# Sheet2.net
KiCad netlist of a schematic drawn in Altium Designer
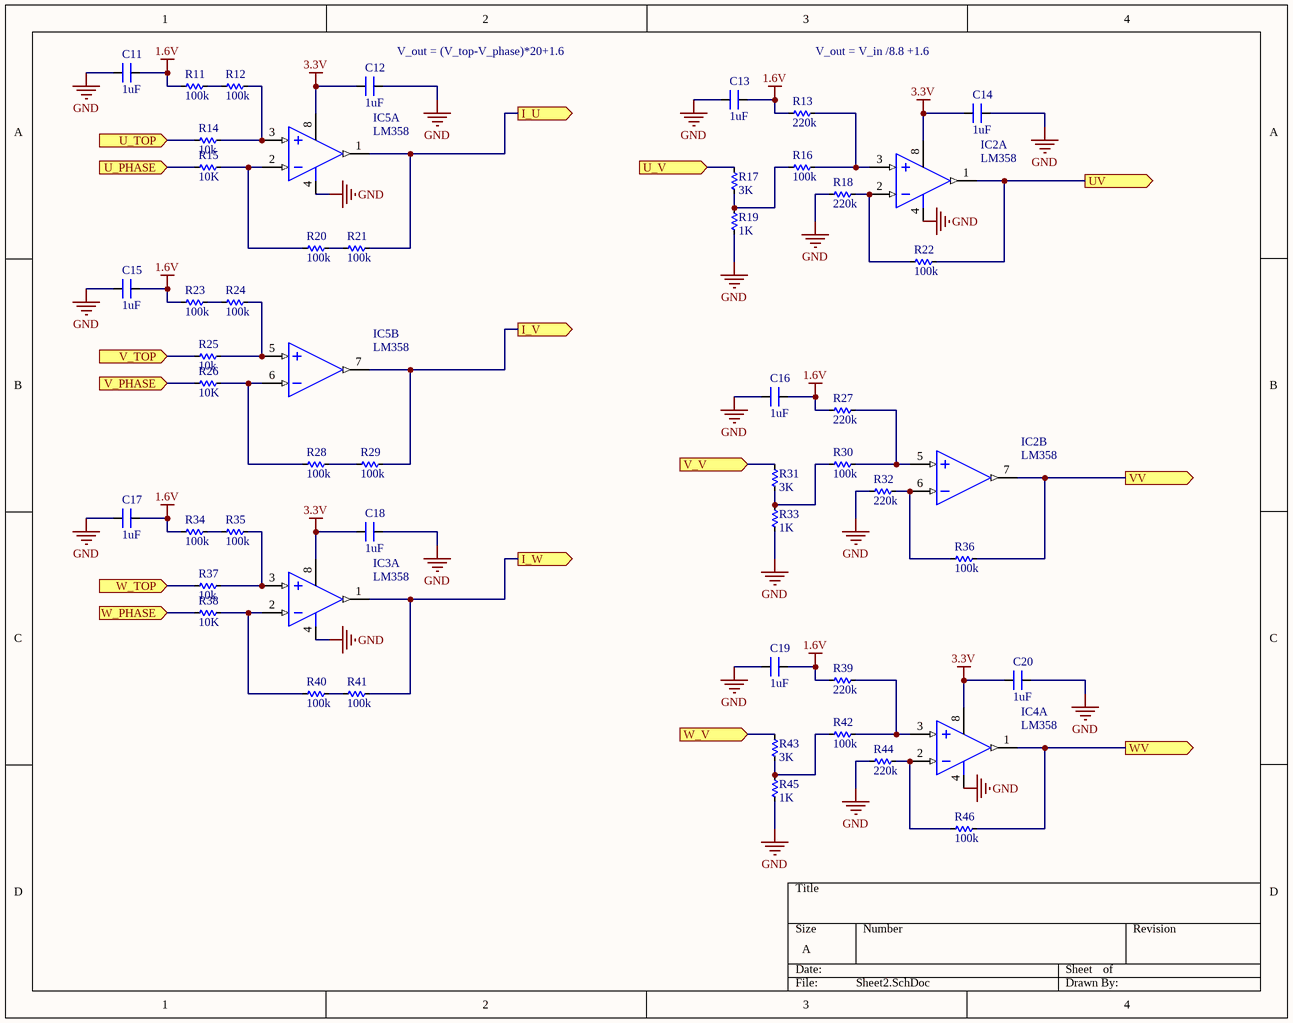
[diagram p0: Sheet2.SchDoc]

(export (version "E")
  (design (tool "Eeschema 10.0.6"))
  (components
    (comp (ref "C11")
      (value "1uF")
      (footprint "CN1")
      (description "Cap np  1pF - 472pF")
      (libsource (lib "syhaunguyen") (part "CN1"))
    )
    (comp (ref "C12")
      (value "1uF")
      (footprint "CN1")
      (description "Cap np  1pF - 472pF")
      (libsource (lib "syhaunguyen") (part "CN1"))
    )
    (comp (ref "C13")
      (value "1uF")
      (footprint "CN1")
      (description "Cap np  1pF - 472pF")
      (libsource (lib "syhaunguyen") (part "CN1"))
    )
    (comp (ref "C14")
      (value "1uF")
      (footprint "CN1")
      (description "Cap np  1pF - 472pF")
      (libsource (lib "syhaunguyen") (part "CN1"))
    )
    (comp (ref "C15")
      (value "1uF")
      (footprint "CN1")
      (description "Cap np  1pF - 472pF")
      (libsource (lib "syhaunguyen") (part "CN1"))
    )
    (comp (ref "C16")
      (value "1uF")
      (footprint "CN1")
      (description "Cap np  1pF - 472pF")
      (libsource (lib "syhaunguyen") (part "CN1"))
    )
    (comp (ref "C17")
      (value "1uF")
      (footprint "CN1")
      (description "Cap np  1pF - 472pF")
      (libsource (lib "syhaunguyen") (part "CN1"))
    )
    (comp (ref "C18")
      (value "1uF")
      (footprint "CN1")
      (description "Cap np  1pF - 472pF")
      (libsource (lib "syhaunguyen") (part "CN1"))
    )
    (comp (ref "C19")
      (value "1uF")
      (footprint "CN1")
      (description "Cap np  1pF - 472pF")
      (libsource (lib "syhaunguyen") (part "CN1"))
    )
    (comp (ref "C20")
      (value "1uF")
      (footprint "CN1")
      (description "Cap np  1pF - 472pF")
      (libsource (lib "syhaunguyen") (part "CN1"))
    )
    (comp (ref "IC2")
      (value "LM358")
      (footprint "DIP8")
      (description "Low-Power Dual Operational Amplifier")
      (libsource (lib "LIBRARY") (part "LM358"))
    )
    (comp (ref "IC3")
      (value "LM358")
      (footprint "DIP8")
      (description "Low-Power Dual Operational Amplifier")
      (libsource (lib "LIBRARY") (part "LM358"))
    )
    (comp (ref "IC4")
      (value "LM358")
      (footprint "DIP8")
      (description "Low-Power Dual Operational Amplifier")
      (libsource (lib "LIBRARY") (part "LM358"))
    )
    (comp (ref "IC5")
      (value "LM358")
      (footprint "DIP8")
      (description "Low-Power Dual Operational Amplifier")
      (libsource (lib "LIBRARY") (part "LM358"))
    )
    (comp (ref "R11")
      (value "100k")
      (footprint "RES-1/2W")
      (description "Res")
      (fields
        (field (name "MANUFACTURER") "Generic Components")
        (field (name "PUBLISHER") "Altium Hobart Technology Centre")
      )
      (libsource (lib "LIBRARY1") (part "Res"))
    )
    (comp (ref "R12")
      (value "100k")
      (footprint "RES-1/2W")
      (description "Res")
      (fields
        (field (name "MANUFACTURER") "Generic Components")
        (field (name "PUBLISHER") "Altium Hobart Technology Centre")
      )
      (libsource (lib "LIBRARY1") (part "Res"))
    )
    (comp (ref "R13")
      (value "220k")
      (footprint "RES-1/2W")
      (description "Res")
      (fields
        (field (name "MANUFACTURER") "Generic Components")
        (field (name "PUBLISHER") "Altium Hobart Technology Centre")
      )
      (libsource (lib "LIBRARY1") (part "Res"))
    )
    (comp (ref "R14")
      (value "10k")
      (footprint "RES-1/2W")
      (description "Res")
      (fields
        (field (name "MANUFACTURER") "Generic Components")
        (field (name "PUBLISHER") "Altium Hobart Technology Centre")
      )
      (libsource (lib "LIBRARY1") (part "Res"))
    )
    (comp (ref "R15")
      (value "10K")
      (footprint "RES-1/2W")
      (description "Res")
      (fields
        (field (name "MANUFACTURER") "Generic Components")
        (field (name "PUBLISHER") "Altium Hobart Technology Centre")
      )
      (libsource (lib "LIBRARY1") (part "Res"))
    )
    (comp (ref "R16")
      (value "100k")
      (footprint "RES-1/2W")
      (description "Res")
      (fields
        (field (name "MANUFACTURER") "Generic Components")
        (field (name "PUBLISHER") "Altium Hobart Technology Centre")
      )
      (libsource (lib "LIBRARY1") (part "Res"))
    )
    (comp (ref "R17")
      (value "3K")
      (footprint "RES-1/2W")
      (description "Res")
      (fields
        (field (name "MANUFACTURER") "Generic Components")
        (field (name "PUBLISHER") "Altium Hobart Technology Centre")
      )
      (libsource (lib "LIBRARY1") (part "Res"))
    )
    (comp (ref "R18")
      (value "220k")
      (footprint "RES-1/2W")
      (description "Res")
      (fields
        (field (name "MANUFACTURER") "Generic Components")
        (field (name "PUBLISHER") "Altium Hobart Technology Centre")
      )
      (libsource (lib "LIBRARY1") (part "Res"))
    )
    (comp (ref "R19")
      (value "1K")
      (footprint "RES-1/2W")
      (description "Res")
      (fields
        (field (name "MANUFACTURER") "Generic Components")
        (field (name "PUBLISHER") "Altium Hobart Technology Centre")
      )
      (libsource (lib "LIBRARY1") (part "Res"))
    )
    (comp (ref "R20")
      (value "100k")
      (footprint "RES-1/2W")
      (description "Res")
      (fields
        (field (name "MANUFACTURER") "Generic Components")
        (field (name "PUBLISHER") "Altium Hobart Technology Centre")
      )
      (libsource (lib "LIBRARY1") (part "Res"))
    )
    (comp (ref "R21")
      (value "100k")
      (footprint "RES-1/2W")
      (description "Res")
      (fields
        (field (name "MANUFACTURER") "Generic Components")
        (field (name "PUBLISHER") "Altium Hobart Technology Centre")
      )
      (libsource (lib "LIBRARY1") (part "Res"))
    )
    (comp (ref "R22")
      (value "100k")
      (footprint "RES-1/2W")
      (description "Res")
      (fields
        (field (name "MANUFACTURER") "Generic Components")
        (field (name "PUBLISHER") "Altium Hobart Technology Centre")
      )
      (libsource (lib "LIBRARY1") (part "Res"))
    )
    (comp (ref "R23")
      (value "100k")
      (footprint "RES-1/2W")
      (description "Res")
      (fields
        (field (name "MANUFACTURER") "Generic Components")
        (field (name "PUBLISHER") "Altium Hobart Technology Centre")
      )
      (libsource (lib "LIBRARY1") (part "Res"))
    )
    (comp (ref "R24")
      (value "100k")
      (footprint "RES-1/2W")
      (description "Res")
      (fields
        (field (name "MANUFACTURER") "Generic Components")
        (field (name "PUBLISHER") "Altium Hobart Technology Centre")
      )
      (libsource (lib "LIBRARY1") (part "Res"))
    )
    (comp (ref "R25")
      (value "10k")
      (footprint "RES-1/2W")
      (description "Res")
      (fields
        (field (name "MANUFACTURER") "Generic Components")
        (field (name "PUBLISHER") "Altium Hobart Technology Centre")
      )
      (libsource (lib "LIBRARY1") (part "Res"))
    )
    (comp (ref "R26")
      (value "10K")
      (footprint "RES-1/2W")
      (description "Res")
      (fields
        (field (name "MANUFACTURER") "Generic Components")
        (field (name "PUBLISHER") "Altium Hobart Technology Centre")
      )
      (libsource (lib "LIBRARY1") (part "Res"))
    )
    (comp (ref "R27")
      (value "220k")
      (footprint "RES-1/2W")
      (description "Res")
      (fields
        (field (name "MANUFACTURER") "Generic Components")
        (field (name "PUBLISHER") "Altium Hobart Technology Centre")
      )
      (libsource (lib "LIBRARY1") (part "Res"))
    )
    (comp (ref "R28")
      (value "100k")
      (footprint "RES-1/2W")
      (description "Res")
      (fields
        (field (name "MANUFACTURER") "Generic Components")
        (field (name "PUBLISHER") "Altium Hobart Technology Centre")
      )
      (libsource (lib "LIBRARY1") (part "Res"))
    )
    (comp (ref "R29")
      (value "100k")
      (footprint "RES-1/2W")
      (description "Res")
      (fields
        (field (name "MANUFACTURER") "Generic Components")
        (field (name "PUBLISHER") "Altium Hobart Technology Centre")
      )
      (libsource (lib "LIBRARY1") (part "Res"))
    )
    (comp (ref "R30")
      (value "100k")
      (footprint "RES-1/2W")
      (description "Res")
      (fields
        (field (name "MANUFACTURER") "Generic Components")
        (field (name "PUBLISHER") "Altium Hobart Technology Centre")
      )
      (libsource (lib "LIBRARY1") (part "Res"))
    )
    (comp (ref "R31")
      (value "3K")
      (footprint "RES-1/2W")
      (description "Res")
      (fields
        (field (name "MANUFACTURER") "Generic Components")
        (field (name "PUBLISHER") "Altium Hobart Technology Centre")
      )
      (libsource (lib "LIBRARY1") (part "Res"))
    )
    (comp (ref "R32")
      (value "220k")
      (footprint "RES-1/2W")
      (description "Res")
      (fields
        (field (name "MANUFACTURER") "Generic Components")
        (field (name "PUBLISHER") "Altium Hobart Technology Centre")
      )
      (libsource (lib "LIBRARY1") (part "Res"))
    )
    (comp (ref "R33")
      (value "1K")
      (footprint "RES-1/2W")
      (description "Res")
      (fields
        (field (name "MANUFACTURER") "Generic Components")
        (field (name "PUBLISHER") "Altium Hobart Technology Centre")
      )
      (libsource (lib "LIBRARY1") (part "Res"))
    )
    (comp (ref "R34")
      (value "100k")
      (footprint "RES-1/2W")
      (description "Res")
      (fields
        (field (name "MANUFACTURER") "Generic Components")
        (field (name "PUBLISHER") "Altium Hobart Technology Centre")
      )
      (libsource (lib "LIBRARY1") (part "Res"))
    )
    (comp (ref "R35")
      (value "100k")
      (footprint "RES-1/2W")
      (description "Res")
      (fields
        (field (name "MANUFACTURER") "Generic Components")
        (field (name "PUBLISHER") "Altium Hobart Technology Centre")
      )
      (libsource (lib "LIBRARY1") (part "Res"))
    )
    (comp (ref "R36")
      (value "100k")
      (footprint "RES-1/2W")
      (description "Res")
      (fields
        (field (name "MANUFACTURER") "Generic Components")
        (field (name "PUBLISHER") "Altium Hobart Technology Centre")
      )
      (libsource (lib "LIBRARY1") (part "Res"))
    )
    (comp (ref "R37")
      (value "10k")
      (footprint "RES-1/2W")
      (description "Res")
      (fields
        (field (name "MANUFACTURER") "Generic Components")
        (field (name "PUBLISHER") "Altium Hobart Technology Centre")
      )
      (libsource (lib "LIBRARY1") (part "Res"))
    )
    (comp (ref "R38")
      (value "10K")
      (footprint "RES-1/2W")
      (description "Res")
      (fields
        (field (name "MANUFACTURER") "Generic Components")
        (field (name "PUBLISHER") "Altium Hobart Technology Centre")
      )
      (libsource (lib "LIBRARY1") (part "Res"))
    )
    (comp (ref "R39")
      (value "220k")
      (footprint "RES-1/2W")
      (description "Res")
      (fields
        (field (name "MANUFACTURER") "Generic Components")
        (field (name "PUBLISHER") "Altium Hobart Technology Centre")
      )
      (libsource (lib "LIBRARY1") (part "Res"))
    )
    (comp (ref "R40")
      (value "100k")
      (footprint "RES-1/2W")
      (description "Res")
      (fields
        (field (name "MANUFACTURER") "Generic Components")
        (field (name "PUBLISHER") "Altium Hobart Technology Centre")
      )
      (libsource (lib "LIBRARY1") (part "Res"))
    )
    (comp (ref "R41")
      (value "100k")
      (footprint "RES-1/2W")
      (description "Res")
      (fields
        (field (name "MANUFACTURER") "Generic Components")
        (field (name "PUBLISHER") "Altium Hobart Technology Centre")
      )
      (libsource (lib "LIBRARY1") (part "Res"))
    )
    (comp (ref "R42")
      (value "100k")
      (footprint "RES-1/2W")
      (description "Res")
      (fields
        (field (name "MANUFACTURER") "Generic Components")
        (field (name "PUBLISHER") "Altium Hobart Technology Centre")
      )
      (libsource (lib "LIBRARY1") (part "Res"))
    )
    (comp (ref "R43")
      (value "3K")
      (footprint "RES-1/2W")
      (description "Res")
      (fields
        (field (name "MANUFACTURER") "Generic Components")
        (field (name "PUBLISHER") "Altium Hobart Technology Centre")
      )
      (libsource (lib "LIBRARY1") (part "Res"))
    )
    (comp (ref "R44")
      (value "220k")
      (footprint "RES-1/2W")
      (description "Res")
      (fields
        (field (name "MANUFACTURER") "Generic Components")
        (field (name "PUBLISHER") "Altium Hobart Technology Centre")
      )
      (libsource (lib "LIBRARY1") (part "Res"))
    )
    (comp (ref "R45")
      (value "1K")
      (footprint "RES-1/2W")
      (description "Res")
      (fields
        (field (name "MANUFACTURER") "Generic Components")
        (field (name "PUBLISHER") "Altium Hobart Technology Centre")
      )
      (libsource (lib "LIBRARY1") (part "Res"))
    )
    (comp (ref "R46")
      (value "100k")
      (footprint "RES-1/2W")
      (description "Res")
      (fields
        (field (name "MANUFACTURER") "Generic Components")
        (field (name "PUBLISHER") "Altium Hobart Technology Centre")
      )
      (libsource (lib "LIBRARY1") (part "Res"))
    )
  )
  (nets
    (net (code "1") (name "/I_U") (class "Default")
      (node (ref "IC5") (pin "1") (pinfunction "OUT_1") (pintype "output"))
      (node (ref "R21") (pin "1") (pinfunction "1_1") (pintype "passive"))
    )
    (net (code "2") (name "/I_V") (class "Default")
      (node (ref "IC5") (pin "7") (pinfunction "OUT_7") (pintype "output"))
      (node (ref "R29") (pin "1") (pinfunction "1_1") (pintype "passive"))
    )
    (net (code "3") (name "/I_W") (class "Default")
      (node (ref "IC3") (pin "1") (pinfunction "OUT_1") (pintype "output"))
      (node (ref "R41") (pin "1") (pinfunction "1_1") (pintype "passive"))
    )
    (net (code "4") (name "/UV") (class "Default")
      (node (ref "IC2") (pin "1") (pinfunction "OUT_1") (pintype "output"))
      (node (ref "R22") (pin "1") (pinfunction "1_1") (pintype "passive"))
    )
    (net (code "5") (name "/U_PHASE") (class "Default")
      (node (ref "R15") (pin "2") (pinfunction "2_2") (pintype "passive"))
    )
    (net (code "6") (name "/U_TOP") (class "Default")
      (node (ref "R14") (pin "2") (pinfunction "2_2") (pintype "passive"))
    )
    (net (code "7") (name "/U_V") (class "Default")
      (node (ref "R17") (pin "1") (pinfunction "1_1") (pintype "passive"))
    )
    (net (code "8") (name "/VV") (class "Default")
      (node (ref "IC2") (pin "7") (pinfunction "OUT_7") (pintype "output"))
      (node (ref "R36") (pin "1") (pinfunction "1_1") (pintype "passive"))
    )
    (net (code "9") (name "/V_PHASE") (class "Default")
      (node (ref "R26") (pin "2") (pinfunction "2_2") (pintype "passive"))
    )
    (net (code "10") (name "/V_TOP") (class "Default")
      (node (ref "R25") (pin "2") (pinfunction "2_2") (pintype "passive"))
    )
    (net (code "11") (name "/V_V") (class "Default")
      (node (ref "R31") (pin "1") (pinfunction "1_1") (pintype "passive"))
    )
    (net (code "12") (name "/WV") (class "Default")
      (node (ref "IC4") (pin "1") (pinfunction "OUT_1") (pintype "output"))
      (node (ref "R46") (pin "1") (pinfunction "1_1") (pintype "passive"))
    )
    (net (code "13") (name "/W_PHASE") (class "Default")
      (node (ref "R38") (pin "2") (pinfunction "2_2") (pintype "passive"))
    )
    (net (code "14") (name "/W_TOP") (class "Default")
      (node (ref "R37") (pin "2") (pinfunction "2_2") (pintype "passive"))
    )
    (net (code "15") (name "/W_V") (class "Default")
      (node (ref "R43") (pin "1") (pinfunction "1_1") (pintype "passive"))
    )
    (net (code "16") (name "1.6V") (class "Default")
      (node (ref "C11") (pin "2") (pinfunction "2_2") (pintype "passive"))
      (node (ref "C13") (pin "2") (pinfunction "2_2") (pintype "passive"))
      (node (ref "C15") (pin "2") (pinfunction "2_2") (pintype "passive"))
      (node (ref "C16") (pin "2") (pinfunction "2_2") (pintype "passive"))
      (node (ref "C17") (pin "2") (pinfunction "2_2") (pintype "passive"))
      (node (ref "C19") (pin "2") (pinfunction "2_2") (pintype "passive"))
      (node (ref "R11") (pin "2") (pinfunction "2_2") (pintype "passive"))
      (node (ref "R13") (pin "2") (pinfunction "2_2") (pintype "passive"))
      (node (ref "R23") (pin "2") (pinfunction "2_2") (pintype "passive"))
      (node (ref "R27") (pin "2") (pinfunction "2_2") (pintype "passive"))
      (node (ref "R34") (pin "2") (pinfunction "2_2") (pintype "passive"))
      (node (ref "R39") (pin "2") (pinfunction "2_2") (pintype "passive"))
    )
    (net (code "17") (name "3.3V") (class "Default")
      (node (ref "C12") (pin "1") (pinfunction "1_1") (pintype "passive"))
      (node (ref "C14") (pin "1") (pinfunction "1_1") (pintype "passive"))
      (node (ref "C18") (pin "1") (pinfunction "1_1") (pintype "passive"))
      (node (ref "C20") (pin "1") (pinfunction "1_1") (pintype "passive"))
      (node (ref "IC2") (pin "8") (pinfunction "+V_8") (pintype "passive"))
      (node (ref "IC3") (pin "8") (pinfunction "+V_8") (pintype "passive"))
      (node (ref "IC4") (pin "8") (pinfunction "+V_8") (pintype "passive"))
      (node (ref "IC5") (pin "8") (pinfunction "+V_8") (pintype "passive"))
    )
    (net (code "18") (name "GND") (class "Default")
      (node (ref "C11") (pin "1") (pinfunction "1_1") (pintype "passive"))
      (node (ref "C12") (pin "2") (pinfunction "2_2") (pintype "passive"))
      (node (ref "C13") (pin "1") (pinfunction "1_1") (pintype "passive"))
      (node (ref "C14") (pin "2") (pinfunction "2_2") (pintype "passive"))
      (node (ref "C15") (pin "1") (pinfunction "1_1") (pintype "passive"))
      (node (ref "C16") (pin "1") (pinfunction "1_1") (pintype "passive"))
      (node (ref "C17") (pin "1") (pinfunction "1_1") (pintype "passive"))
      (node (ref "C18") (pin "2") (pinfunction "2_2") (pintype "passive"))
      (node (ref "C19") (pin "1") (pinfunction "1_1") (pintype "passive"))
      (node (ref "C20") (pin "2") (pinfunction "2_2") (pintype "passive"))
      (node (ref "IC2") (pin "4") (pinfunction "-V_4") (pintype "passive"))
      (node (ref "IC3") (pin "4") (pinfunction "-V_4") (pintype "passive"))
      (node (ref "IC4") (pin "4") (pinfunction "-V_4") (pintype "passive"))
      (node (ref "IC5") (pin "4") (pinfunction "-V_4") (pintype "passive"))
      (node (ref "R18") (pin "2") (pinfunction "2_2") (pintype "passive"))
      (node (ref "R19") (pin "2") (pinfunction "2_2") (pintype "passive"))
      (node (ref "R32") (pin "2") (pinfunction "2_2") (pintype "passive"))
      (node (ref "R33") (pin "2") (pinfunction "2_2") (pintype "passive"))
      (node (ref "R44") (pin "2") (pinfunction "2_2") (pintype "passive"))
      (node (ref "R45") (pin "2") (pinfunction "2_2") (pintype "passive"))
    )
    (net (code "19") (name "Net-(IC2A-IN+)") (class "Default")
      (node (ref "IC2") (pin "3") (pinfunction "IN+_3") (pintype "input"))
      (node (ref "R13") (pin "1") (pinfunction "1_1") (pintype "passive"))
      (node (ref "R16") (pin "1") (pinfunction "1_1") (pintype "passive"))
    )
    (net (code "20") (name "Net-(IC2A-IN-)") (class "Default")
      (node (ref "IC2") (pin "2") (pinfunction "IN-_2") (pintype "input"))
      (node (ref "R18") (pin "1") (pinfunction "1_1") (pintype "passive"))
      (node (ref "R22") (pin "2") (pinfunction "2_2") (pintype "passive"))
    )
    (net (code "21") (name "Net-(IC2B-IN+)") (class "Default")
      (node (ref "IC2") (pin "5") (pinfunction "IN+_5") (pintype "input"))
      (node (ref "R27") (pin "1") (pinfunction "1_1") (pintype "passive"))
      (node (ref "R30") (pin "1") (pinfunction "1_1") (pintype "passive"))
    )
    (net (code "22") (name "Net-(IC2B-IN-)") (class "Default")
      (node (ref "IC2") (pin "6") (pinfunction "IN-_6") (pintype "input"))
      (node (ref "R32") (pin "1") (pinfunction "1_1") (pintype "passive"))
      (node (ref "R36") (pin "2") (pinfunction "2_2") (pintype "passive"))
    )
    (net (code "23") (name "Net-(IC3A-IN+)") (class "Default")
      (node (ref "IC3") (pin "3") (pinfunction "IN+_3") (pintype "input"))
      (node (ref "R35") (pin "1") (pinfunction "1_1") (pintype "passive"))
      (node (ref "R37") (pin "1") (pinfunction "1_1") (pintype "passive"))
    )
    (net (code "24") (name "Net-(IC3A-IN-)") (class "Default")
      (node (ref "IC3") (pin "2") (pinfunction "IN-_2") (pintype "input"))
      (node (ref "R38") (pin "1") (pinfunction "1_1") (pintype "passive"))
      (node (ref "R40") (pin "2") (pinfunction "2_2") (pintype "passive"))
    )
    (net (code "25") (name "Net-(IC4A-IN+)") (class "Default")
      (node (ref "IC4") (pin "3") (pinfunction "IN+_3") (pintype "input"))
      (node (ref "R39") (pin "1") (pinfunction "1_1") (pintype "passive"))
      (node (ref "R42") (pin "1") (pinfunction "1_1") (pintype "passive"))
    )
    (net (code "26") (name "Net-(IC4A-IN-)") (class "Default")
      (node (ref "IC4") (pin "2") (pinfunction "IN-_2") (pintype "input"))
      (node (ref "R44") (pin "1") (pinfunction "1_1") (pintype "passive"))
      (node (ref "R46") (pin "2") (pinfunction "2_2") (pintype "passive"))
    )
    (net (code "27") (name "Net-(IC5A-IN+)") (class "Default")
      (node (ref "IC5") (pin "3") (pinfunction "IN+_3") (pintype "input"))
      (node (ref "R12") (pin "1") (pinfunction "1_1") (pintype "passive"))
      (node (ref "R14") (pin "1") (pinfunction "1_1") (pintype "passive"))
    )
    (net (code "28") (name "Net-(IC5A-IN-)") (class "Default")
      (node (ref "IC5") (pin "2") (pinfunction "IN-_2") (pintype "input"))
      (node (ref "R15") (pin "1") (pinfunction "1_1") (pintype "passive"))
      (node (ref "R20") (pin "2") (pinfunction "2_2") (pintype "passive"))
    )
    (net (code "29") (name "Net-(IC5B-IN+)") (class "Default")
      (node (ref "IC5") (pin "5") (pinfunction "IN+_5") (pintype "input"))
      (node (ref "R24") (pin "1") (pinfunction "1_1") (pintype "passive"))
      (node (ref "R25") (pin "1") (pinfunction "1_1") (pintype "passive"))
    )
    (net (code "30") (name "Net-(IC5B-IN-)") (class "Default")
      (node (ref "IC5") (pin "6") (pinfunction "IN-_6") (pintype "input"))
      (node (ref "R26") (pin "1") (pinfunction "1_1") (pintype "passive"))
      (node (ref "R28") (pin "2") (pinfunction "2_2") (pintype "passive"))
    )
    (net (code "31") (name "Net-(R11-Pad1)") (class "Default")
      (node (ref "R11") (pin "1") (pinfunction "1_1") (pintype "passive"))
      (node (ref "R12") (pin "2") (pinfunction "2_2") (pintype "passive"))
    )
    (net (code "32") (name "Net-(R16-Pad2)") (class "Default")
      (node (ref "R16") (pin "2") (pinfunction "2_2") (pintype "passive"))
      (node (ref "R17") (pin "2") (pinfunction "2_2") (pintype "passive"))
      (node (ref "R19") (pin "1") (pinfunction "1_1") (pintype "passive"))
    )
    (net (code "33") (name "Net-(R20-Pad1)") (class "Default")
      (node (ref "R20") (pin "1") (pinfunction "1_1") (pintype "passive"))
      (node (ref "R21") (pin "2") (pinfunction "2_2") (pintype "passive"))
    )
    (net (code "34") (name "Net-(R23-Pad1)") (class "Default")
      (node (ref "R23") (pin "1") (pinfunction "1_1") (pintype "passive"))
      (node (ref "R24") (pin "2") (pinfunction "2_2") (pintype "passive"))
    )
    (net (code "35") (name "Net-(R28-Pad1)") (class "Default")
      (node (ref "R28") (pin "1") (pinfunction "1_1") (pintype "passive"))
      (node (ref "R29") (pin "2") (pinfunction "2_2") (pintype "passive"))
    )
    (net (code "36") (name "Net-(R30-Pad2)") (class "Default")
      (node (ref "R30") (pin "2") (pinfunction "2_2") (pintype "passive"))
      (node (ref "R31") (pin "2") (pinfunction "2_2") (pintype "passive"))
      (node (ref "R33") (pin "1") (pinfunction "1_1") (pintype "passive"))
    )
    (net (code "37") (name "Net-(R34-Pad1)") (class "Default")
      (node (ref "R34") (pin "1") (pinfunction "1_1") (pintype "passive"))
      (node (ref "R35") (pin "2") (pinfunction "2_2") (pintype "passive"))
    )
    (net (code "38") (name "Net-(R40-Pad1)") (class "Default")
      (node (ref "R40") (pin "1") (pinfunction "1_1") (pintype "passive"))
      (node (ref "R41") (pin "2") (pinfunction "2_2") (pintype "passive"))
    )
    (net (code "39") (name "Net-(R42-Pad2)") (class "Default")
      (node (ref "R42") (pin "2") (pinfunction "2_2") (pintype "passive"))
      (node (ref "R43") (pin "2") (pinfunction "2_2") (pintype "passive"))
      (node (ref "R45") (pin "1") (pinfunction "1_1") (pintype "passive"))
    )
  )
)
